# schematicjson.net
KiCad netlist of a schematic drawn in EasyEDA
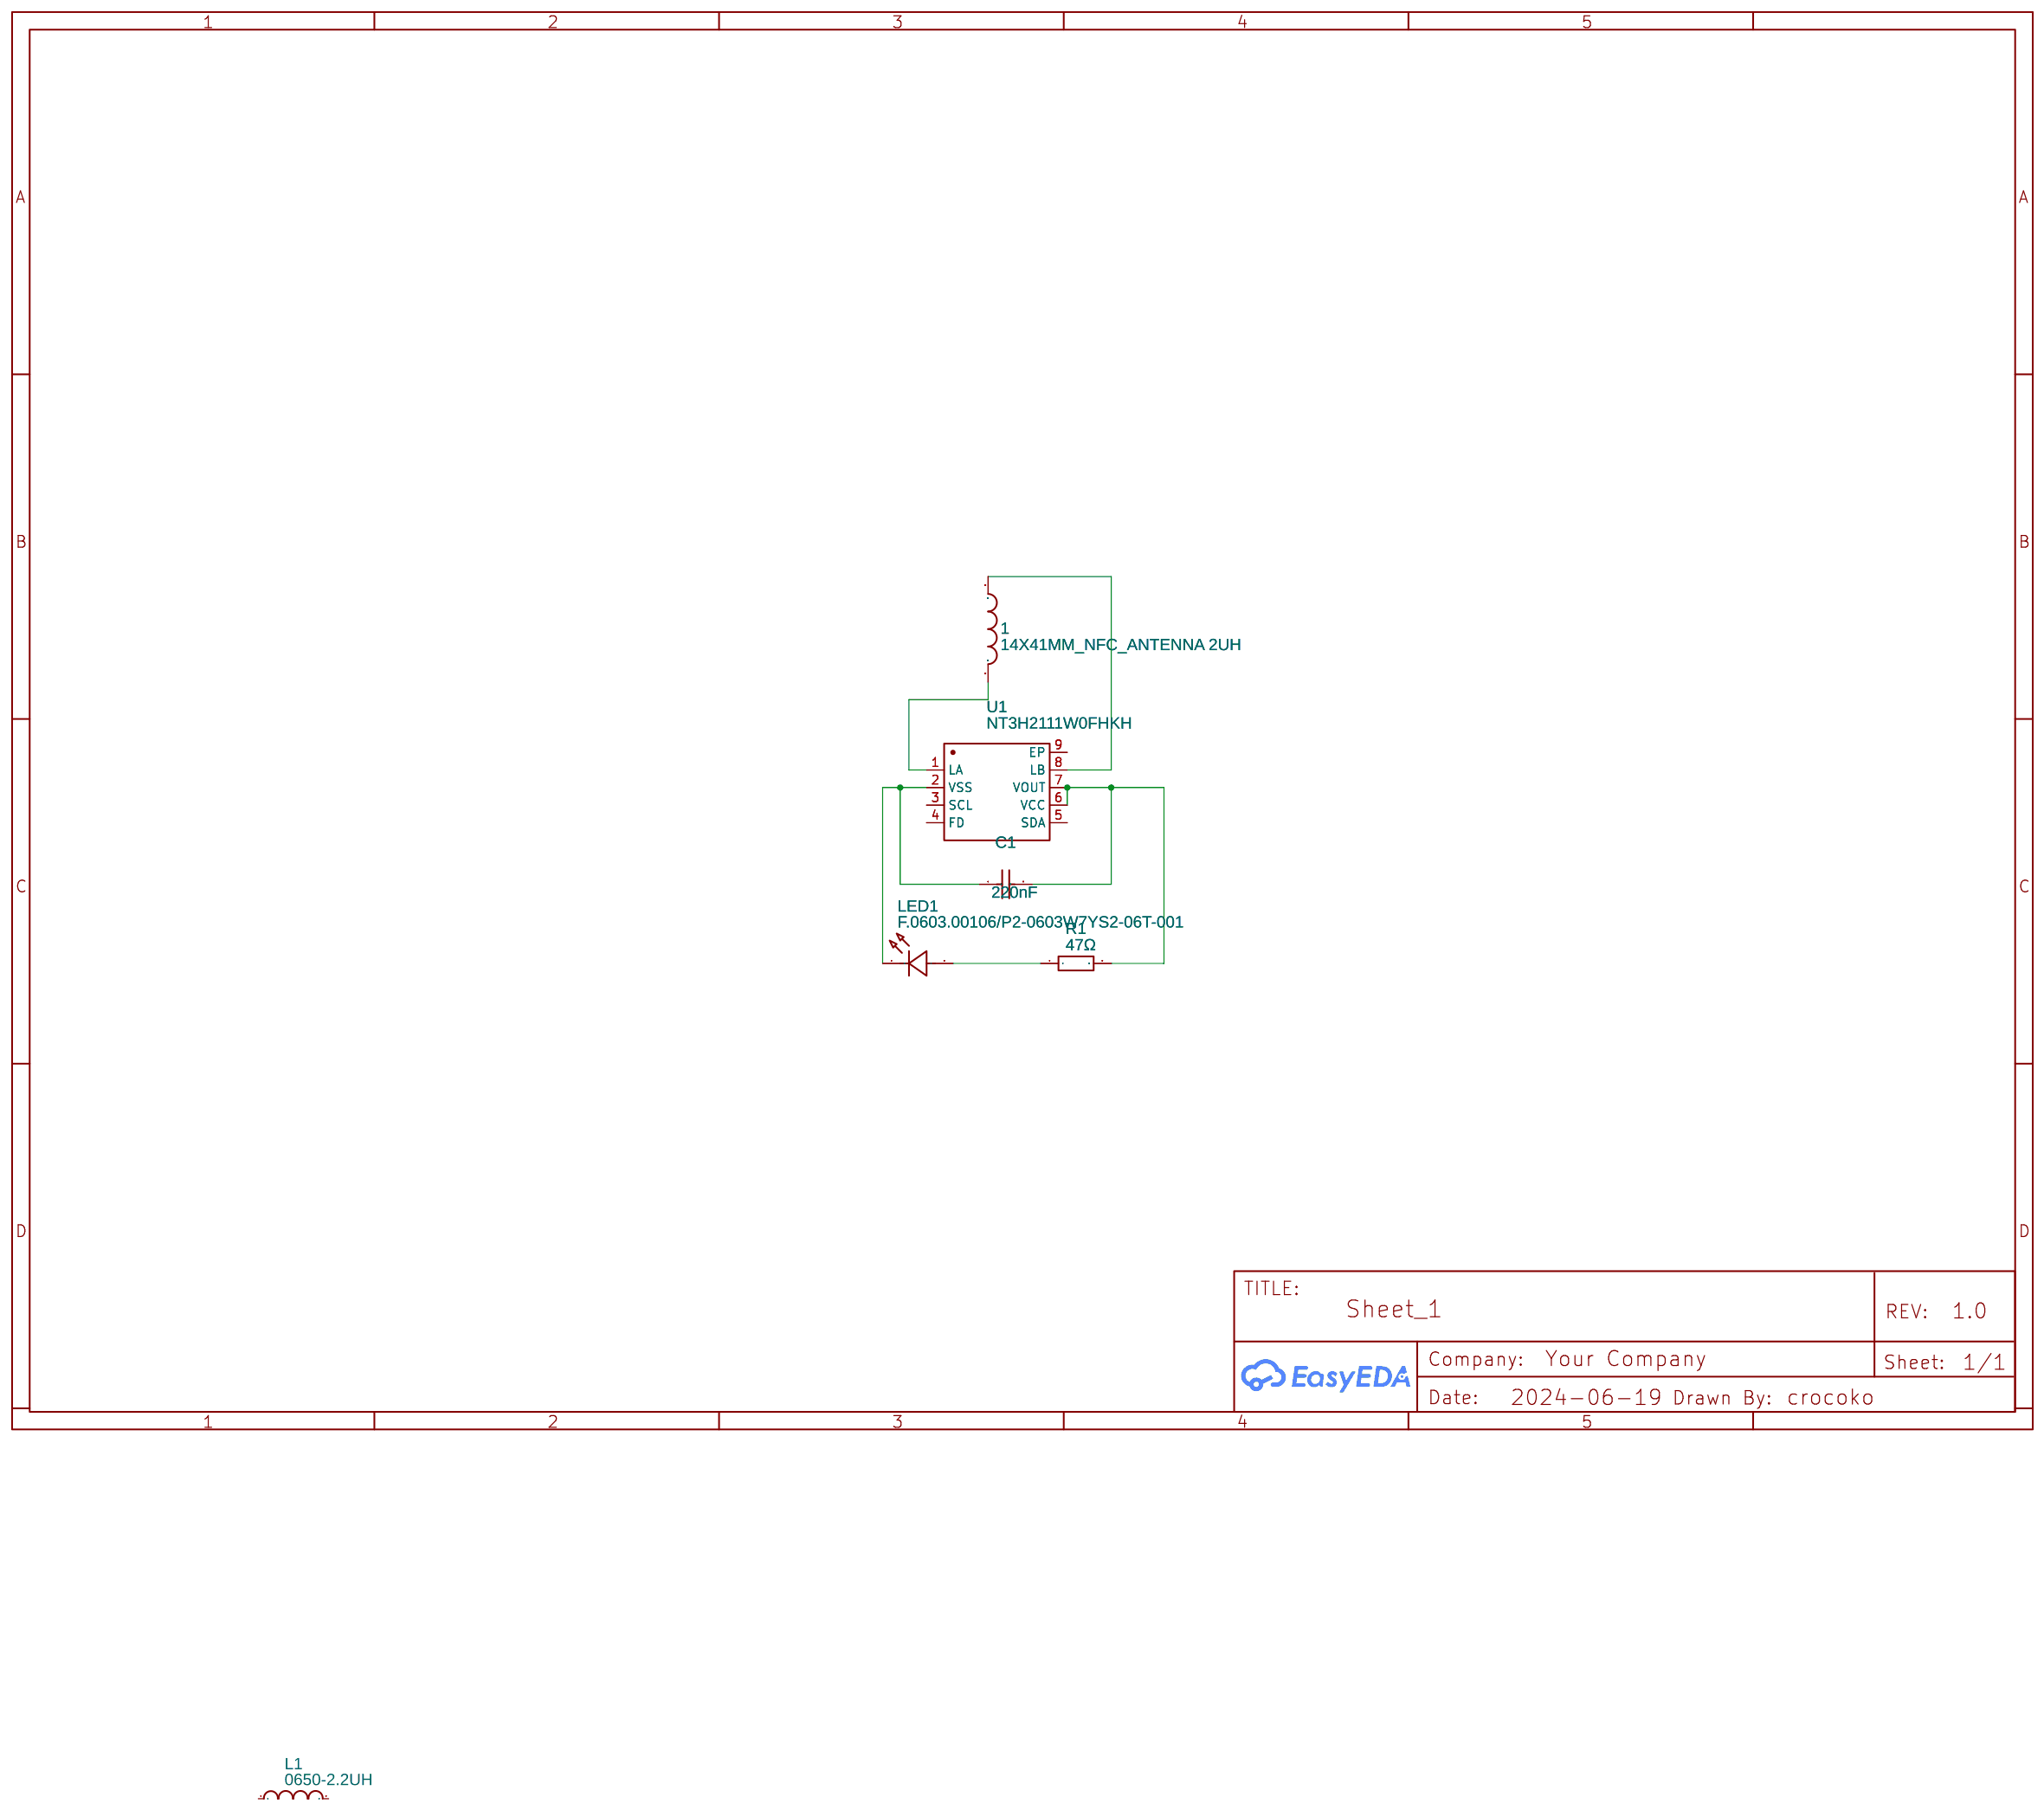
[diagram p0: schematic sheet]

(export (version "E")
  (design (tool "Eeschema 10.0.6"))
  (components
    (comp (ref "1") (value "14X41MM_NFC_ANTENNA 2UH") (libsource (lib "") (part "14X41MM_NFC_ANTENNA 2UH")))
    (comp (ref "C1")
      (value "220nF")
      (fields
        (field (name "Manufacturer Part") "CL10B224KA8NNNC")
        (field (name "Manufacturer") "SAMSUNG(三星)")
      )
      (libsource (lib "") (part "CL10B224KA8NNNC"))
    )
    (comp (ref "L1") (value "0650-2.2UH") (libsource (lib "") (part "0650-2.2UH")))
    (comp (ref "LED1")
      (value "F.0603.00106/P2-0603W7YS2-06T-001")
      (fields (field (name "Manufacturer") "TUOZHAN(拓展光电)"))
      (libsource (lib "") (part "F.0603.00106/P2-0603W7YS2-06T-001"))
    )
    (comp (ref "R1")
      (value "47Ω")
      (fields
        (field (name "Manufacturer Part") "0603WAF470JT5E")
        (field (name "Manufacturer") "UNI-ROYAL(厚声)")
      )
      (libsource (lib "") (part "0603WAF470JT5E"))
    )
    (comp (ref "U1")
      (value "NT3H2111W0FHKH")
      (fields (field (name "Manufacturer") "NXP(恩智浦)"))
      (libsource (lib "") (part "NT3H2111W0FHKH"))
    )
  )
  (nets
    (net (code "1") (name "Net-(LED1-A)") (class "Default")
      (node (ref "LED1") (pin "2") (pinfunction "A_2") (pintype "unspecified"))
      (node (ref "R1") (pin "1") (pinfunction "1_1") (pintype "input"))
    )
    (net (code "2") (name "Net-(LED1-K)") (class "Default")
      (node (ref "C1") (pin "1") (pinfunction "1_1") (pintype "input"))
      (node (ref "LED1") (pin "1") (pinfunction "K_1") (pintype "unspecified"))
      (node (ref "U1") (pin "2") (pinfunction "VSS_2") (pintype "unspecified"))
    )
    (net (code "3") (name "Net-(U1-LA)") (class "Default")
      (node (ref "1") (pin "P$2") (pinfunction "P$2_P$2") (pintype "bidirectional"))
      (node (ref "U1") (pin "1") (pinfunction "LA_1") (pintype "unspecified"))
    )
    (net (code "4") (name "Net-(U1-LB)") (class "Default")
      (node (ref "1") (pin "P$1") (pinfunction "P$1_P$1") (pintype "bidirectional"))
      (node (ref "U1") (pin "8") (pinfunction "LB_8") (pintype "unspecified"))
    )
    (net (code "5") (name "Net-(U1-VCC)") (class "Default")
      (node (ref "C1") (pin "2") (pinfunction "2_2") (pintype "input"))
      (node (ref "R1") (pin "2") (pinfunction "2_2") (pintype "input"))
      (node (ref "U1") (pin "6") (pinfunction "VCC_6") (pintype "unspecified"))
      (node (ref "U1") (pin "7") (pinfunction "VOUT_7") (pintype "unspecified"))
    )
    (net (code "6") (name "unconnected-(L1-Pad1)") (class "Default")
      (node (ref "L1") (pin "1") (pinfunction "1_1") (pintype "unspecified"))
    )
    (net (code "7") (name "unconnected-(L1-Pad2)") (class "Default")
      (node (ref "L1") (pin "2") (pinfunction "2_2") (pintype "unspecified"))
    )
    (net (code "8") (name "unconnected-(U1-EP-Pad9)") (class "Default")
      (node (ref "U1") (pin "9") (pinfunction "EP_9") (pintype "unspecified"))
    )
    (net (code "9") (name "unconnected-(U1-FD-Pad4)") (class "Default")
      (node (ref "U1") (pin "4") (pinfunction "FD_4") (pintype "unspecified"))
    )
    (net (code "10") (name "unconnected-(U1-SCL-Pad3)") (class "Default")
      (node (ref "U1") (pin "3") (pinfunction "SCL_3") (pintype "unspecified"))
    )
    (net (code "11") (name "unconnected-(U1-SDA-Pad5)") (class "Default")
      (node (ref "U1") (pin "5") (pinfunction "SDA_5") (pintype "unspecified"))
    )
  )
)
